# Schematic.net
KiCad netlist of a schematic drawn in EasyEDA
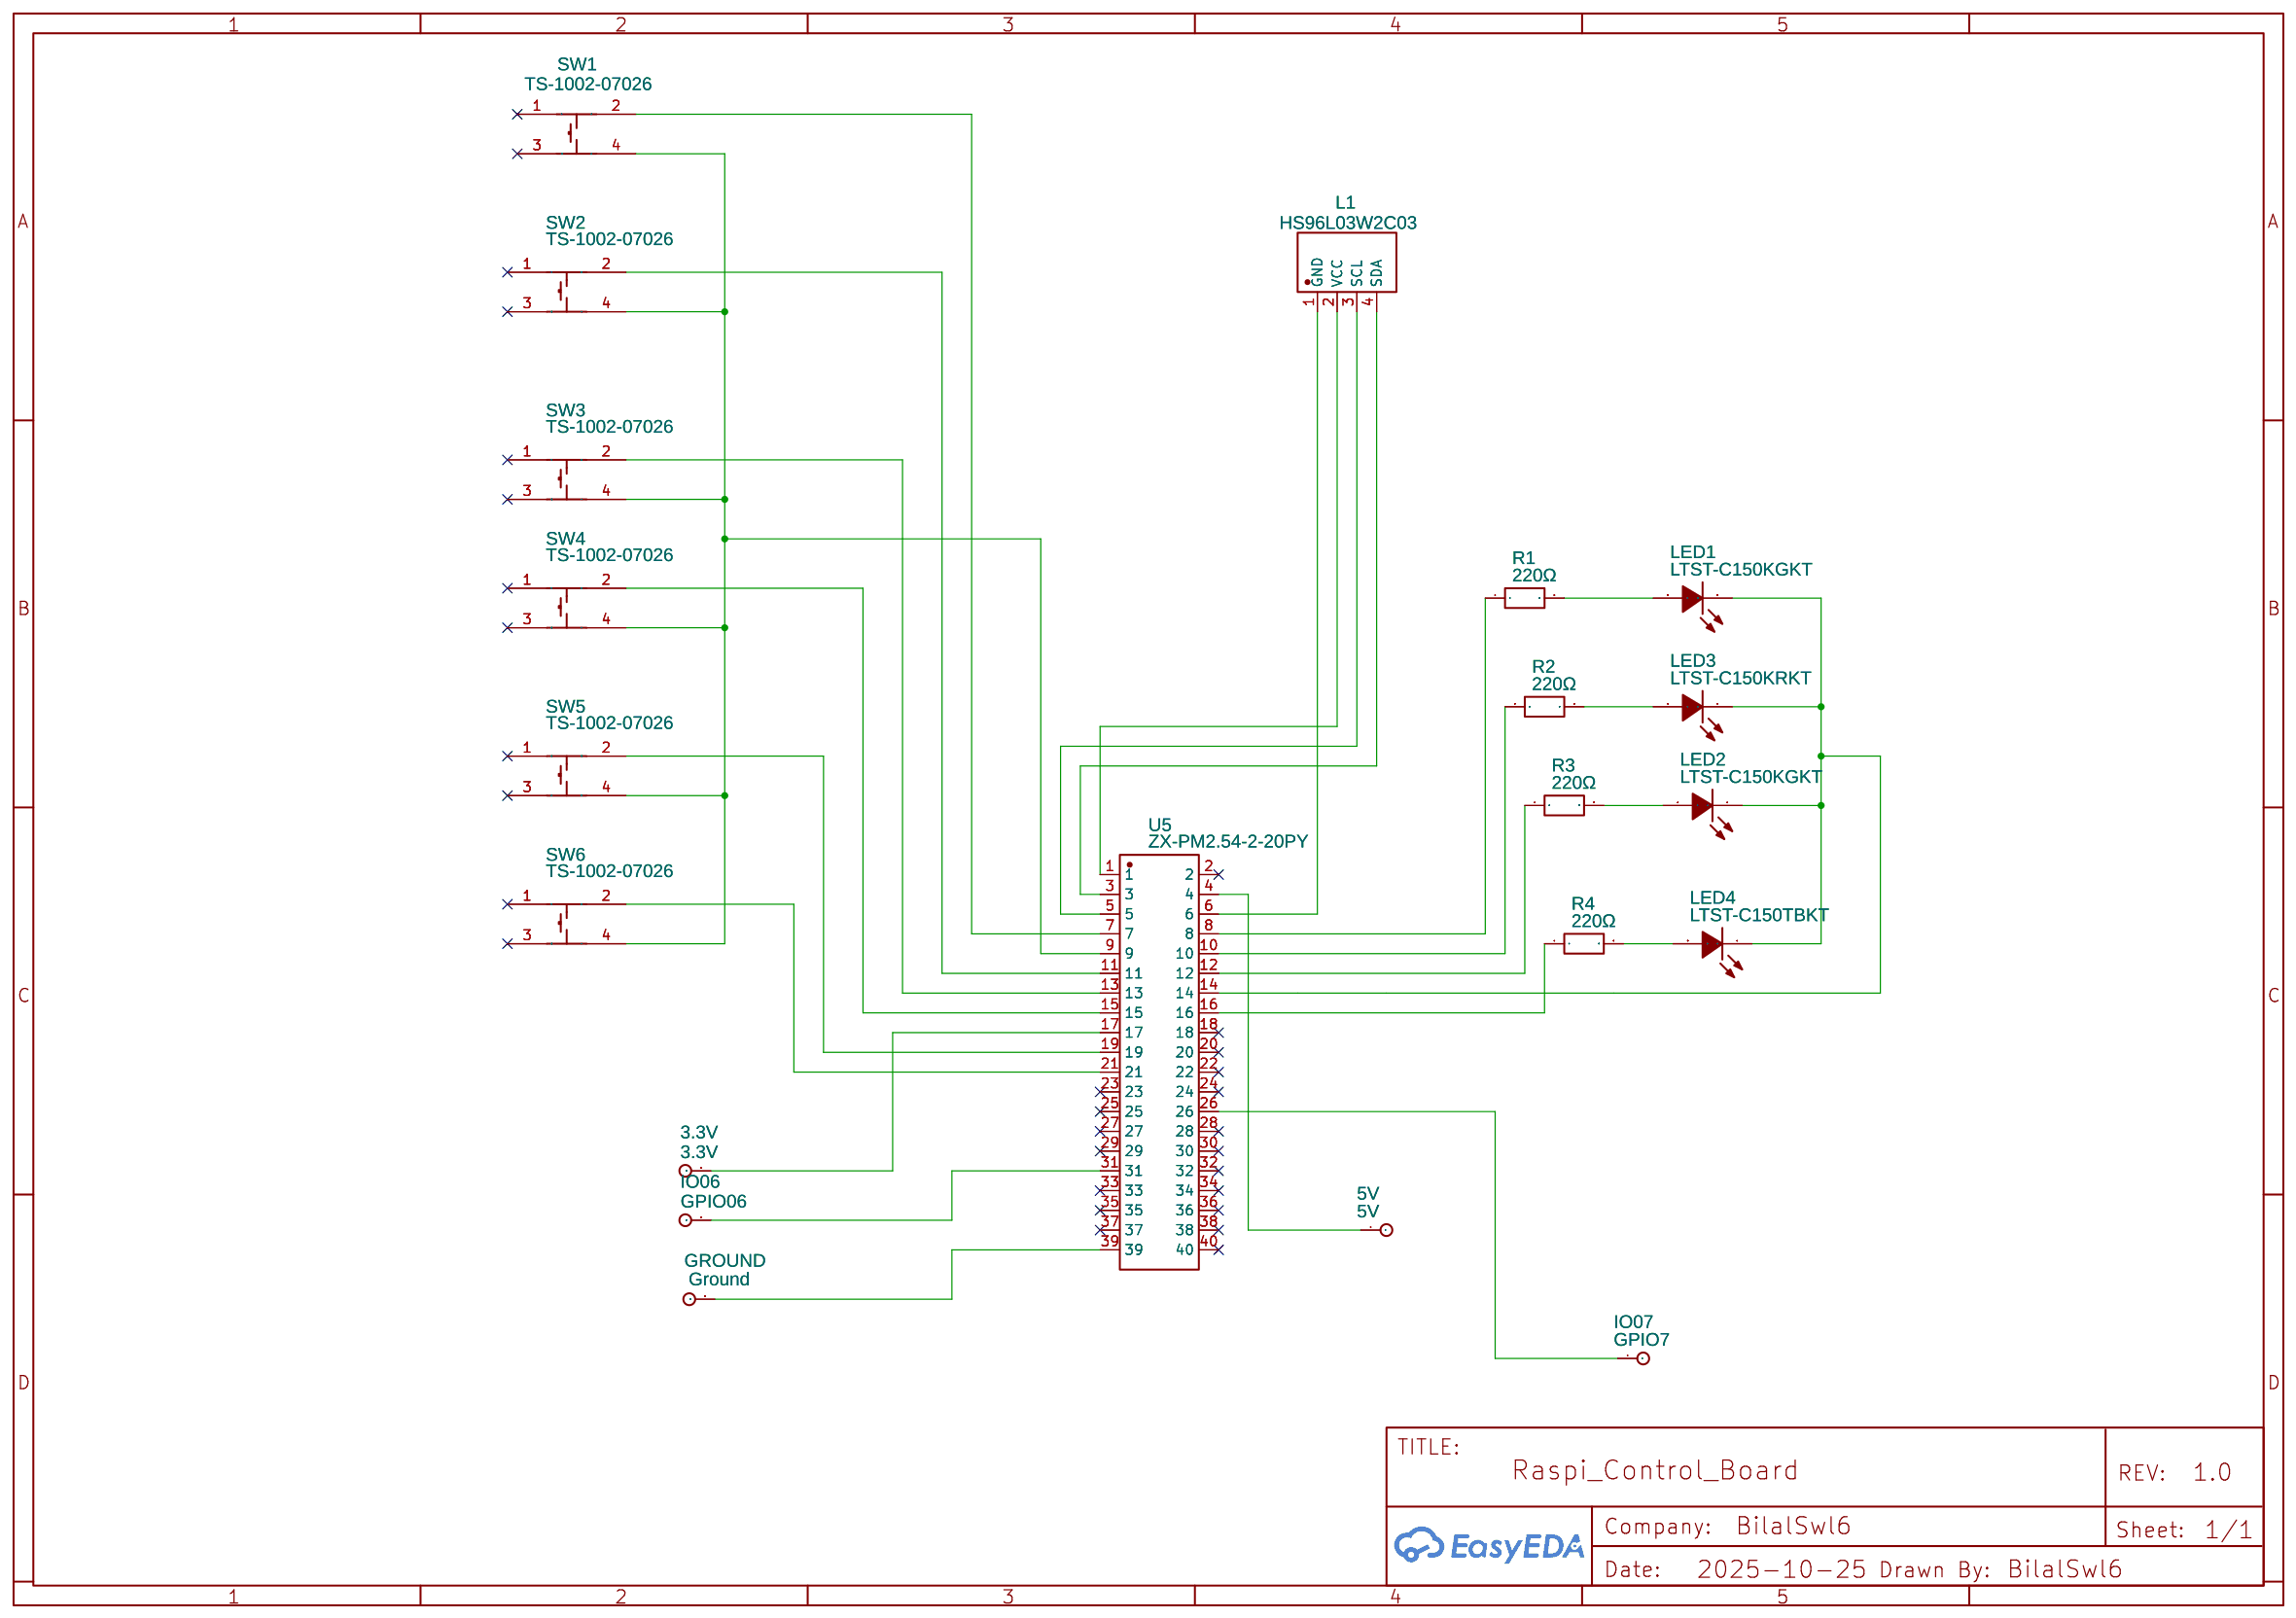
[diagram p0: schematic sheet]

(export (version "E")
  (design (tool "Eeschema 10.0.6"))
  (components
    (comp (ref "3.3V") (value "3.3V") (libsource (lib "") (part "Connector_TestPoint_4")))
    (comp (ref "5V") (value "5V") (libsource (lib "") (part "Connector_TestPoint_1")))
    (comp (ref "GROUND") (value "Ground") (libsource (lib "") (part "Connector_TestPoint_3")))
    (comp (ref "IO06") (value "GPIO06") (libsource (lib "") (part "Connector_TestPoint_2")))
    (comp (ref "IO07") (value "GPIO7") (libsource (lib "") (part "Connector_TestPoint")))
    (comp (ref "L1")
      (value "HS96L03W2C03")
      (fields (field (name "Manufacturer") "HS(汉昇)"))
      (libsource (lib "") (part "HS96L03W2C03"))
    )
    (comp (ref "LED1")
      (value "LTST-C150KGKT")
      (fields (field (name "Manufacturer") "LITEON(光宝)"))
      (libsource (lib "") (part "LTST-C150KGKT"))
    )
    (comp (ref "LED2")
      (value "LTST-C150KGKT")
      (fields (field (name "Manufacturer") "LITEON(光宝)"))
      (libsource (lib "") (part "LTST-C150KGKT"))
    )
    (comp (ref "LED3")
      (value "LTST-C150KRKT")
      (fields (field (name "Manufacturer") "LITEON(光宝)"))
      (libsource (lib "") (part "LTST-C150KRKT"))
    )
    (comp (ref "LED4")
      (value "LTST-C150TBKT")
      (fields (field (name "Manufacturer") "LITEON(光宝)"))
      (libsource (lib "") (part "LTST-C150TBKT"))
    )
    (comp (ref "R1")
      (value "220Ω")
      (fields (field (name "Manufacturer Part") "FRC1206J221 TS") (field (name "Manufacturer") "FOJAN(富捷)"))
      (libsource (lib "") (part "FRC1206J221 TS"))
    )
    (comp (ref "R2")
      (value "220Ω")
      (fields (field (name "Manufacturer Part") "FRC1206J221 TS") (field (name "Manufacturer") "FOJAN(富捷)"))
      (libsource (lib "") (part "FRC1206J221 TS"))
    )
    (comp (ref "R3")
      (value "220Ω")
      (fields (field (name "Manufacturer Part") "FRC1206J221 TS") (field (name "Manufacturer") "FOJAN(富捷)"))
      (libsource (lib "") (part "FRC1206J221 TS"))
    )
    (comp (ref "R4")
      (value "220Ω")
      (fields (field (name "Manufacturer Part") "FRC1206J221 TS") (field (name "Manufacturer") "FOJAN(富捷)"))
      (libsource (lib "") (part "FRC1206J221 TS"))
    )
    (comp (ref "SW1")
      (value "TS-1002-07026")
      (fields (field (name "Manufacturer") "XUNPU(讯普)"))
      (libsource (lib "") (part "TS-1002-07026"))
    )
    (comp (ref "SW2")
      (value "TS-1002-07026")
      (fields (field (name "Manufacturer") "XUNPU(讯普)"))
      (libsource (lib "") (part "TS-1002-07026"))
    )
    (comp (ref "SW3")
      (value "TS-1002-07026")
      (fields (field (name "Manufacturer") "XUNPU(讯普)"))
      (libsource (lib "") (part "TS-1002-07026"))
    )
    (comp (ref "SW4")
      (value "TS-1002-07026")
      (fields (field (name "Manufacturer") "XUNPU(讯普)"))
      (libsource (lib "") (part "TS-1002-07026"))
    )
    (comp (ref "SW5")
      (value "TS-1002-07026")
      (fields (field (name "Manufacturer") "XUNPU(讯普)"))
      (libsource (lib "") (part "TS-1002-07026"))
    )
    (comp (ref "SW6")
      (value "TS-1002-07026")
      (fields (field (name "Manufacturer") "XUNPU(讯普)"))
      (libsource (lib "") (part "TS-1002-07026"))
    )
    (comp (ref "U5")
      (value "ZX-PM2.54-2-20PY")
      (fields (field (name "Manufacturer") "Megastar(兆星)"))
      (libsource (lib "") (part "ZX-PM2.54-2-20PY"))
    )
  )
  (nets
    (net (code "1") (name "Net-(3.3V-Pad1)") (class "Default")
      (node (ref "3.3V") (pin "1") (pinfunction "1_1") (pintype "unspecified"))
      (node (ref "U5") (pin "17") (pinfunction "17_17") (pintype "unspecified"))
    )
    (net (code "2") (name "Net-(5V-Pad1)") (class "Default")
      (node (ref "5V") (pin "1") (pinfunction "1_1") (pintype "unspecified"))
      (node (ref "U5") (pin "4") (pinfunction "4_4") (pintype "unspecified"))
    )
    (net (code "3") (name "Net-(GROUND-Pad1)") (class "Default")
      (node (ref "GROUND") (pin "1") (pinfunction "1_1") (pintype "unspecified"))
      (node (ref "U5") (pin "39") (pinfunction "39_39") (pintype "unspecified"))
    )
    (net (code "4") (name "Net-(IO06-Pad1)") (class "Default")
      (node (ref "IO06") (pin "1") (pinfunction "1_1") (pintype "unspecified"))
      (node (ref "U5") (pin "31") (pinfunction "31_31") (pintype "unspecified"))
    )
    (net (code "5") (name "Net-(IO07-Pad1)") (class "Default")
      (node (ref "IO07") (pin "1") (pinfunction "1_1") (pintype "unspecified"))
      (node (ref "U5") (pin "26") (pinfunction "26_26") (pintype "unspecified"))
    )
    (net (code "6") (name "Net-(L1-GND)") (class "Default")
      (node (ref "L1") (pin "1") (pinfunction "GND_1") (pintype "unspecified"))
      (node (ref "U5") (pin "6") (pinfunction "6_6") (pintype "unspecified"))
    )
    (net (code "7") (name "Net-(L1-SCL)") (class "Default")
      (node (ref "L1") (pin "3") (pinfunction "SCL_3") (pintype "unspecified"))
      (node (ref "U5") (pin "5") (pinfunction "5_5") (pintype "unspecified"))
    )
    (net (code "8") (name "Net-(L1-SDA)") (class "Default")
      (node (ref "L1") (pin "4") (pinfunction "SDA_4") (pintype "unspecified"))
      (node (ref "U5") (pin "3") (pinfunction "3_3") (pintype "unspecified"))
    )
    (net (code "9") (name "Net-(L1-VCC)") (class "Default")
      (node (ref "L1") (pin "2") (pinfunction "VCC_2") (pintype "unspecified"))
      (node (ref "U5") (pin "1") (pinfunction "1_1") (pintype "unspecified"))
    )
    (net (code "10") (name "Net-(LED1-A)") (class "Default")
      (node (ref "LED1") (pin "2") (pinfunction "A_2") (pintype "unspecified"))
      (node (ref "R1") (pin "2") (pinfunction "2_2") (pintype "unspecified"))
    )
    (net (code "11") (name "Net-(LED1-K)") (class "Default")
      (node (ref "LED1") (pin "1") (pinfunction "K_1") (pintype "unspecified"))
      (node (ref "LED2") (pin "1") (pinfunction "K_1") (pintype "unspecified"))
      (node (ref "LED3") (pin "1") (pinfunction "K_1") (pintype "unspecified"))
      (node (ref "LED4") (pin "1") (pinfunction "K_1") (pintype "unspecified"))
      (node (ref "U5") (pin "14") (pinfunction "14_14") (pintype "unspecified"))
    )
    (net (code "12") (name "Net-(LED2-A)") (class "Default")
      (node (ref "LED2") (pin "2") (pinfunction "A_2") (pintype "unspecified"))
      (node (ref "R3") (pin "2") (pinfunction "2_2") (pintype "unspecified"))
    )
    (net (code "13") (name "Net-(LED3-A)") (class "Default")
      (node (ref "LED3") (pin "2") (pinfunction "A_2") (pintype "unspecified"))
      (node (ref "R2") (pin "2") (pinfunction "2_2") (pintype "unspecified"))
    )
    (net (code "14") (name "Net-(LED4-A)") (class "Default")
      (node (ref "LED4") (pin "2") (pinfunction "A_2") (pintype "unspecified"))
      (node (ref "R4") (pin "2") (pinfunction "2_2") (pintype "unspecified"))
    )
    (net (code "15") (name "Net-(R1-Pad1)") (class "Default")
      (node (ref "R1") (pin "1") (pinfunction "1_1") (pintype "unspecified"))
      (node (ref "U5") (pin "8") (pinfunction "8_8") (pintype "unspecified"))
    )
    (net (code "16") (name "Net-(R2-Pad1)") (class "Default")
      (node (ref "R2") (pin "1") (pinfunction "1_1") (pintype "unspecified"))
      (node (ref "U5") (pin "10") (pinfunction "10_10") (pintype "unspecified"))
    )
    (net (code "17") (name "Net-(R3-Pad1)") (class "Default")
      (node (ref "R3") (pin "1") (pinfunction "1_1") (pintype "unspecified"))
      (node (ref "U5") (pin "12") (pinfunction "12_12") (pintype "unspecified"))
    )
    (net (code "18") (name "Net-(R4-Pad1)") (class "Default")
      (node (ref "R4") (pin "1") (pinfunction "1_1") (pintype "unspecified"))
      (node (ref "U5") (pin "16") (pinfunction "16_16") (pintype "unspecified"))
    )
    (net (code "19") (name "Net-(SW1-Pad2)") (class "Default")
      (node (ref "SW1") (pin "2") (pinfunction "2_2") (pintype "unspecified"))
      (node (ref "U5") (pin "7") (pinfunction "7_7") (pintype "unspecified"))
    )
    (net (code "20") (name "Net-(SW1-Pad4)") (class "Default")
      (node (ref "SW1") (pin "4") (pinfunction "4_4") (pintype "unspecified"))
      (node (ref "SW2") (pin "4") (pinfunction "4_4") (pintype "unspecified"))
      (node (ref "SW3") (pin "4") (pinfunction "4_4") (pintype "unspecified"))
      (node (ref "SW4") (pin "4") (pinfunction "4_4") (pintype "unspecified"))
      (node (ref "SW5") (pin "4") (pinfunction "4_4") (pintype "unspecified"))
      (node (ref "SW6") (pin "4") (pinfunction "4_4") (pintype "unspecified"))
      (node (ref "U5") (pin "9") (pinfunction "9_9") (pintype "unspecified"))
    )
    (net (code "21") (name "Net-(SW2-Pad2)") (class "Default")
      (node (ref "SW2") (pin "2") (pinfunction "2_2") (pintype "unspecified"))
      (node (ref "U5") (pin "11") (pinfunction "11_11") (pintype "unspecified"))
    )
    (net (code "22") (name "Net-(SW3-Pad2)") (class "Default")
      (node (ref "SW3") (pin "2") (pinfunction "2_2") (pintype "unspecified"))
      (node (ref "U5") (pin "13") (pinfunction "13_13") (pintype "unspecified"))
    )
    (net (code "23") (name "Net-(SW4-Pad2)") (class "Default")
      (node (ref "SW4") (pin "2") (pinfunction "2_2") (pintype "unspecified"))
      (node (ref "U5") (pin "15") (pinfunction "15_15") (pintype "unspecified"))
    )
    (net (code "24") (name "Net-(SW5-Pad2)") (class "Default")
      (node (ref "SW5") (pin "2") (pinfunction "2_2") (pintype "unspecified"))
      (node (ref "U5") (pin "19") (pinfunction "19_19") (pintype "unspecified"))
    )
    (net (code "25") (name "Net-(SW6-Pad2)") (class "Default")
      (node (ref "SW6") (pin "2") (pinfunction "2_2") (pintype "unspecified"))
      (node (ref "U5") (pin "21") (pinfunction "21_21") (pintype "unspecified"))
    )
    (net (code "26") (name "unconnected-(SW1-Pad1)") (class "Default")
      (node (ref "SW1") (pin "1") (pinfunction "1_1") (pintype "unspecified+no_connect"))
    )
    (net (code "27") (name "unconnected-(SW1-Pad3)") (class "Default")
      (node (ref "SW1") (pin "3") (pinfunction "3_3") (pintype "unspecified+no_connect"))
    )
    (net (code "28") (name "unconnected-(SW2-Pad1)") (class "Default")
      (node (ref "SW2") (pin "1") (pinfunction "1_1") (pintype "unspecified+no_connect"))
    )
    (net (code "29") (name "unconnected-(SW2-Pad3)") (class "Default")
      (node (ref "SW2") (pin "3") (pinfunction "3_3") (pintype "unspecified+no_connect"))
    )
    (net (code "30") (name "unconnected-(SW3-Pad1)") (class "Default")
      (node (ref "SW3") (pin "1") (pinfunction "1_1") (pintype "unspecified+no_connect"))
    )
    (net (code "31") (name "unconnected-(SW3-Pad3)") (class "Default")
      (node (ref "SW3") (pin "3") (pinfunction "3_3") (pintype "unspecified+no_connect"))
    )
    (net (code "32") (name "unconnected-(SW4-Pad1)") (class "Default")
      (node (ref "SW4") (pin "1") (pinfunction "1_1") (pintype "unspecified+no_connect"))
    )
    (net (code "33") (name "unconnected-(SW4-Pad3)") (class "Default")
      (node (ref "SW4") (pin "3") (pinfunction "3_3") (pintype "unspecified+no_connect"))
    )
    (net (code "34") (name "unconnected-(SW5-Pad1)") (class "Default")
      (node (ref "SW5") (pin "1") (pinfunction "1_1") (pintype "unspecified+no_connect"))
    )
    (net (code "35") (name "unconnected-(SW5-Pad3)") (class "Default")
      (node (ref "SW5") (pin "3") (pinfunction "3_3") (pintype "unspecified+no_connect"))
    )
    (net (code "36") (name "unconnected-(SW6-Pad1)") (class "Default")
      (node (ref "SW6") (pin "1") (pinfunction "1_1") (pintype "unspecified+no_connect"))
    )
    (net (code "37") (name "unconnected-(SW6-Pad3)") (class "Default")
      (node (ref "SW6") (pin "3") (pinfunction "3_3") (pintype "unspecified+no_connect"))
    )
    (net (code "38") (name "unconnected-(U5-Pad2)") (class "Default")
      (node (ref "U5") (pin "2") (pinfunction "2_2") (pintype "unspecified+no_connect"))
    )
    (net (code "39") (name "unconnected-(U5-Pad18)") (class "Default")
      (node (ref "U5") (pin "18") (pinfunction "18_18") (pintype "unspecified+no_connect"))
    )
    (net (code "40") (name "unconnected-(U5-Pad20)") (class "Default")
      (node (ref "U5") (pin "20") (pinfunction "20_20") (pintype "unspecified+no_connect"))
    )
    (net (code "41") (name "unconnected-(U5-Pad22)") (class "Default")
      (node (ref "U5") (pin "22") (pinfunction "22_22") (pintype "unspecified+no_connect"))
    )
    (net (code "42") (name "unconnected-(U5-Pad23)") (class "Default")
      (node (ref "U5") (pin "23") (pinfunction "23_23") (pintype "unspecified+no_connect"))
    )
    (net (code "43") (name "unconnected-(U5-Pad24)") (class "Default")
      (node (ref "U5") (pin "24") (pinfunction "24_24") (pintype "unspecified+no_connect"))
    )
    (net (code "44") (name "unconnected-(U5-Pad25)") (class "Default")
      (node (ref "U5") (pin "25") (pinfunction "25_25") (pintype "unspecified+no_connect"))
    )
    (net (code "45") (name "unconnected-(U5-Pad27)") (class "Default")
      (node (ref "U5") (pin "27") (pinfunction "27_27") (pintype "unspecified+no_connect"))
    )
    (net (code "46") (name "unconnected-(U5-Pad28)") (class "Default")
      (node (ref "U5") (pin "28") (pinfunction "28_28") (pintype "unspecified+no_connect"))
    )
    (net (code "47") (name "unconnected-(U5-Pad29)") (class "Default")
      (node (ref "U5") (pin "29") (pinfunction "29_29") (pintype "unspecified+no_connect"))
    )
    (net (code "48") (name "unconnected-(U5-Pad30)") (class "Default")
      (node (ref "U5") (pin "30") (pinfunction "30_30") (pintype "unspecified+no_connect"))
    )
    (net (code "49") (name "unconnected-(U5-Pad32)") (class "Default")
      (node (ref "U5") (pin "32") (pinfunction "32_32") (pintype "unspecified+no_connect"))
    )
    (net (code "50") (name "unconnected-(U5-Pad33)") (class "Default")
      (node (ref "U5") (pin "33") (pinfunction "33_33") (pintype "unspecified+no_connect"))
    )
    (net (code "51") (name "unconnected-(U5-Pad34)") (class "Default")
      (node (ref "U5") (pin "34") (pinfunction "34_34") (pintype "unspecified+no_connect"))
    )
    (net (code "52") (name "unconnected-(U5-Pad35)") (class "Default")
      (node (ref "U5") (pin "35") (pinfunction "35_35") (pintype "unspecified+no_connect"))
    )
    (net (code "53") (name "unconnected-(U5-Pad36)") (class "Default")
      (node (ref "U5") (pin "36") (pinfunction "36_36") (pintype "unspecified+no_connect"))
    )
    (net (code "54") (name "unconnected-(U5-Pad37)") (class "Default")
      (node (ref "U5") (pin "37") (pinfunction "37_37") (pintype "unspecified+no_connect"))
    )
    (net (code "55") (name "unconnected-(U5-Pad38)") (class "Default")
      (node (ref "U5") (pin "38") (pinfunction "38_38") (pintype "unspecified+no_connect"))
    )
    (net (code "56") (name "unconnected-(U5-Pad40)") (class "Default")
      (node (ref "U5") (pin "40") (pinfunction "40_40") (pintype "unspecified+no_connect"))
    )
  )
)
